# esp32cam.net
KiCad netlist of a schematic drawn in EAGLE
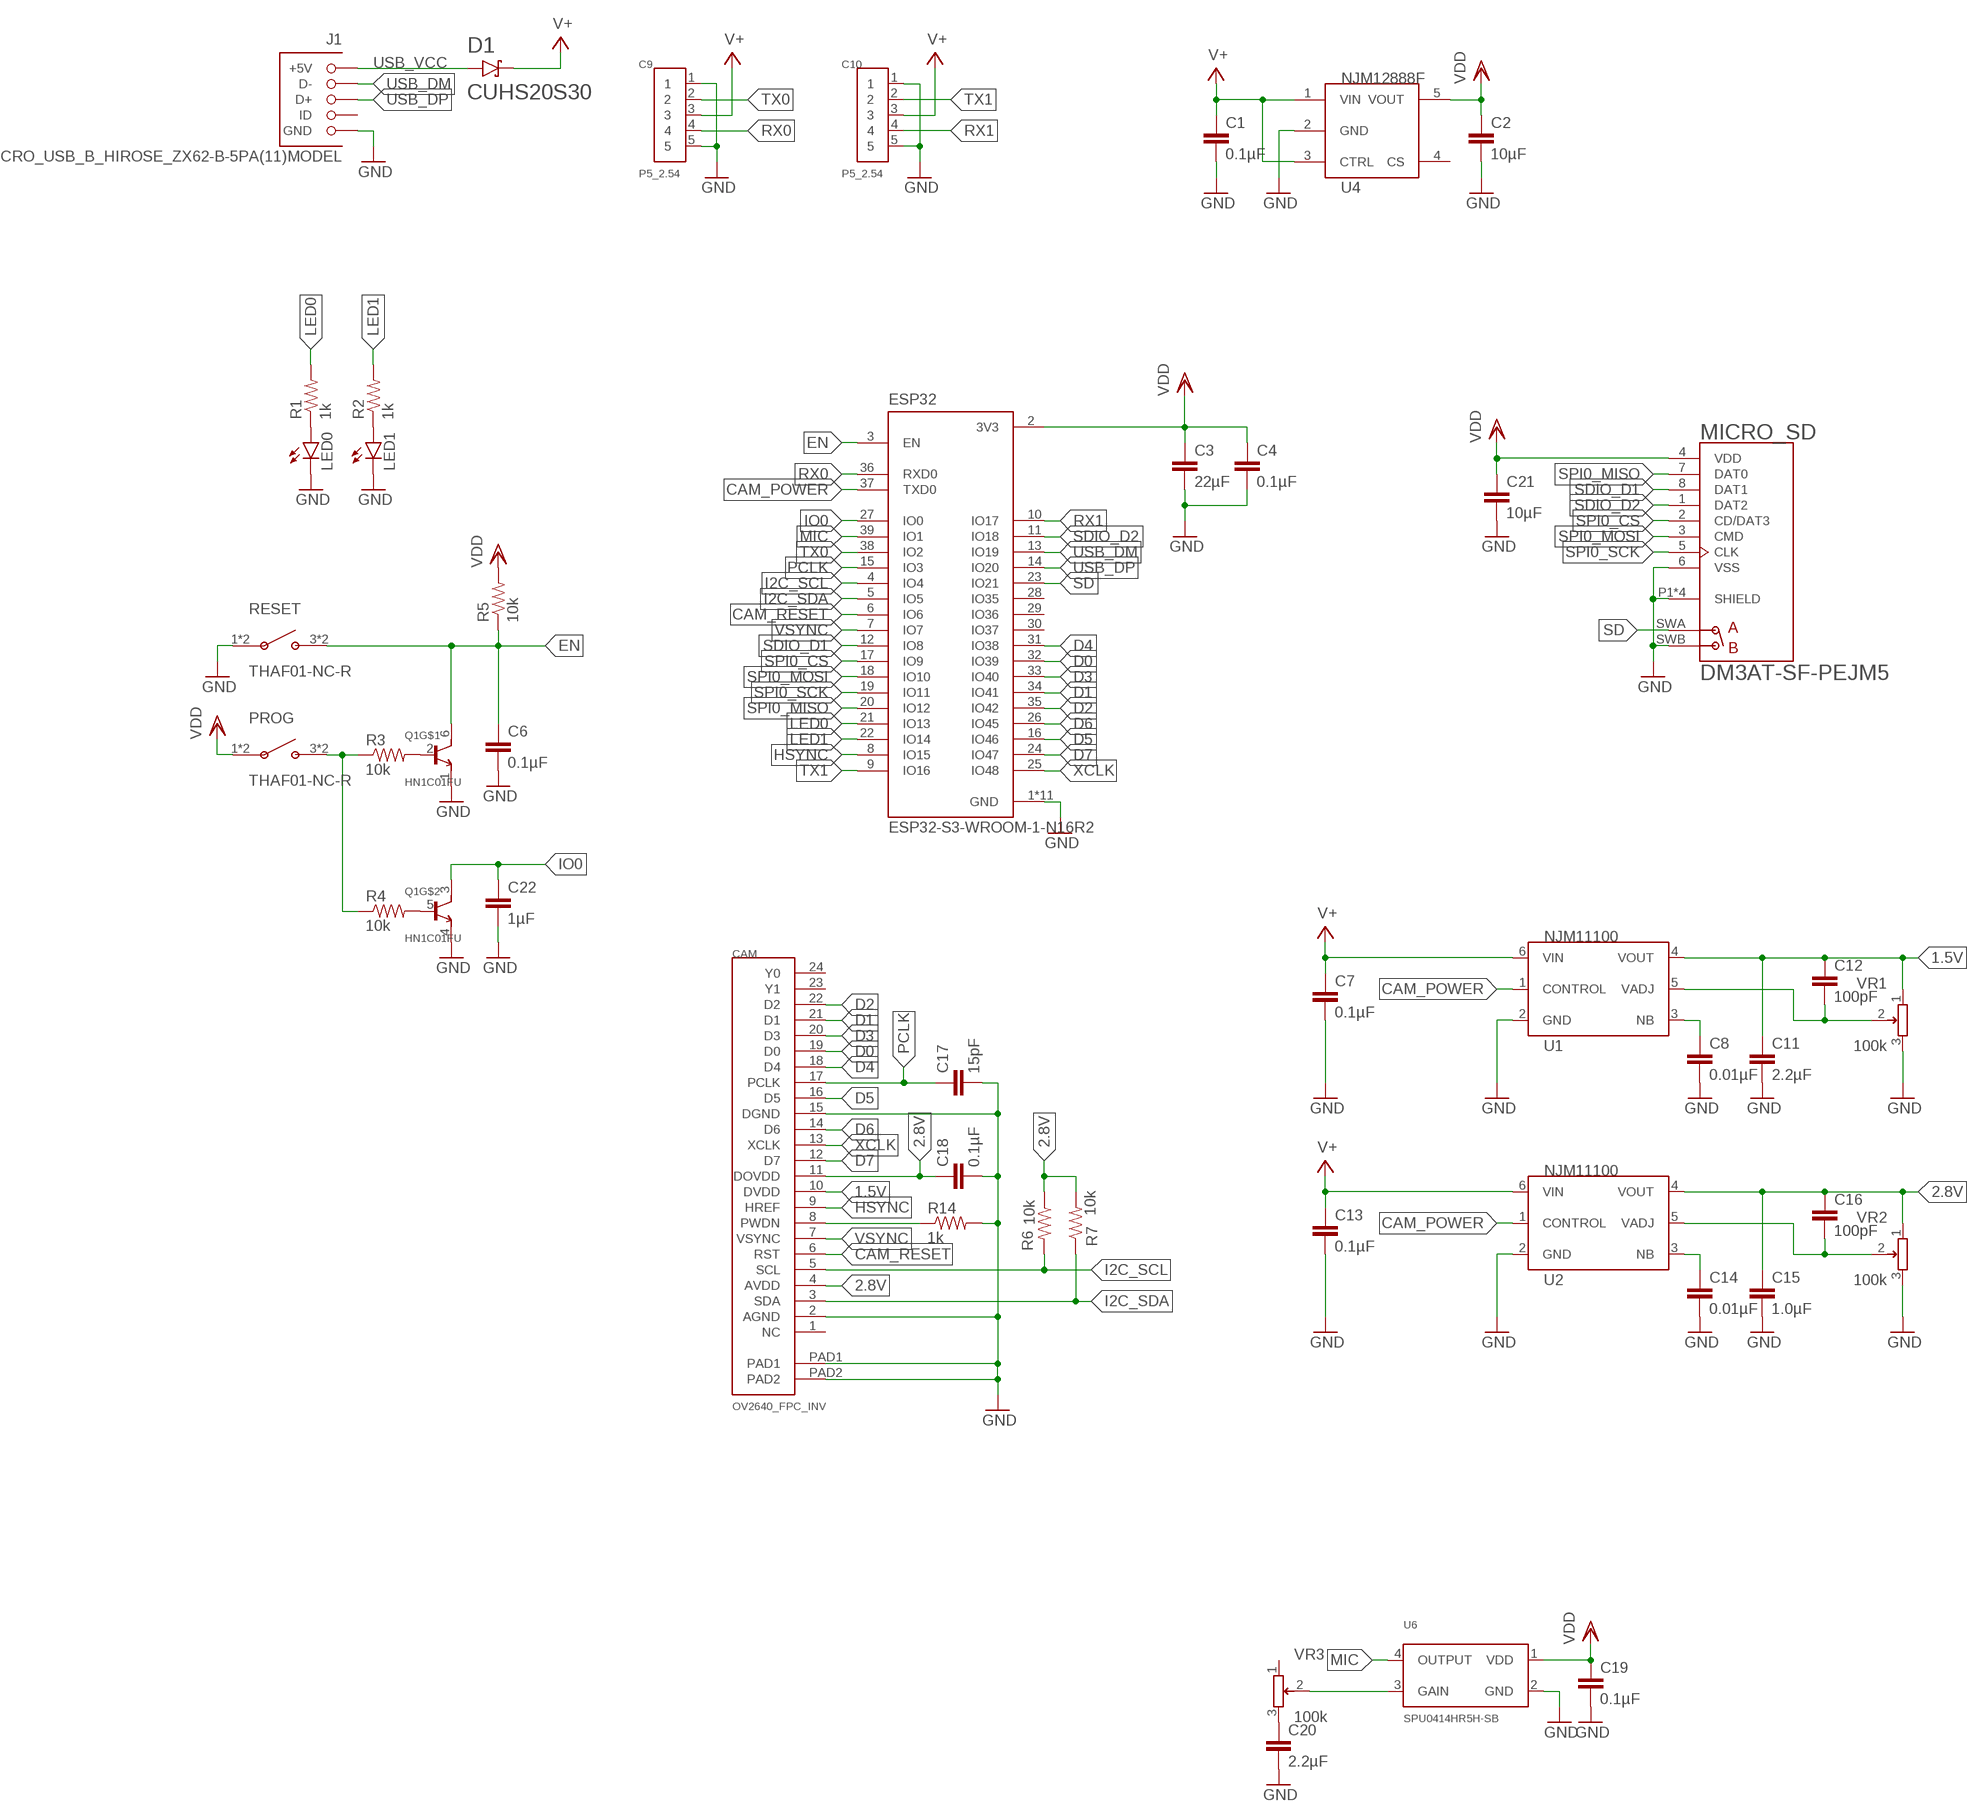
[diagram p0: schematic, sheet 1]

(export (version "E")
  (design (tool "Eeschema 10.0.6"))
  (components
    (comp (ref "C1")
      (value "0.1µF")
      (footprint "eagle-import:C0402")
      (libsource (lib "eagle-import") (part "C-EUC0402"))
    )
    (comp (ref "C2")
      (value "10µF")
      (footprint "eagle-import:C0402")
      (libsource (lib "eagle-import") (part "C-EUC0402"))
    )
    (comp (ref "C3")
      (value "22µF")
      (footprint "eagle-import:C0402")
      (libsource (lib "eagle-import") (part "C-EUC0402"))
    )
    (comp (ref "C4")
      (value "0.1µF")
      (footprint "eagle-import:C0402")
      (libsource (lib "eagle-import") (part "C-EUC0402"))
    )
    (comp (ref "C6")
      (value "0.1µF")
      (footprint "eagle-import:C0402")
      (libsource (lib "eagle-import") (part "C-EUC0402"))
    )
    (comp (ref "C7")
      (value "0.1µF")
      (footprint "eagle-import:C0402")
      (libsource (lib "eagle-import") (part "C-EUC0402"))
    )
    (comp (ref "C8")
      (value "0.01µF")
      (footprint "eagle-import:C0402")
      (libsource (lib "eagle-import") (part "C-EUC0402"))
    )
    (comp (ref "C9")
      (value "P5_2.54")
      (footprint "eagle-import:P5_2.54")
      (libsource (lib "eagle-import") (part "P5_2.54"))
    )
    (comp (ref "C10")
      (value "P5_2.54")
      (footprint "eagle-import:P5_2.54")
      (libsource (lib "eagle-import") (part "P5_2.54"))
    )
    (comp (ref "C11")
      (value "2.2µF")
      (footprint "eagle-import:C0402")
      (libsource (lib "eagle-import") (part "C-EUC0402"))
    )
    (comp (ref "C12")
      (value "100pF")
      (footprint "eagle-import:C0402")
      (libsource (lib "eagle-import") (part "C-EUC0402"))
    )
    (comp (ref "C13")
      (value "0.1µF")
      (footprint "eagle-import:C0402")
      (libsource (lib "eagle-import") (part "C-EUC0402"))
    )
    (comp (ref "C14")
      (value "0.01µF")
      (footprint "eagle-import:C0402")
      (libsource (lib "eagle-import") (part "C-EUC0402"))
    )
    (comp (ref "C15")
      (value "1.0µF")
      (footprint "eagle-import:C0402")
      (libsource (lib "eagle-import") (part "C-EUC0402"))
    )
    (comp (ref "C16")
      (value "100pF")
      (footprint "eagle-import:C0402")
      (libsource (lib "eagle-import") (part "C-EUC0402"))
    )
    (comp (ref "C17")
      (value "15pF")
      (footprint "eagle-import:C0402")
      (libsource (lib "eagle-import") (part "C-EUC0402"))
    )
    (comp (ref "C18")
      (value "0.1µF")
      (footprint "eagle-import:C0402")
      (libsource (lib "eagle-import") (part "C-EUC0402"))
    )
    (comp (ref "C19")
      (value "0.1µF")
      (footprint "eagle-import:C0402")
      (libsource (lib "eagle-import") (part "C-EUC0402"))
    )
    (comp (ref "C20")
      (value "2.2µF")
      (footprint "eagle-import:C0402")
      (libsource (lib "eagle-import") (part "C-EUC0402"))
    )
    (comp (ref "C21")
      (value "10µF")
      (footprint "eagle-import:C0402")
      (libsource (lib "eagle-import") (part "C-EUC0402"))
    )
    (comp (ref "C22")
      (value "1µF")
      (footprint "eagle-import:C0402")
      (libsource (lib "eagle-import") (part "C-EUC0402"))
    )
    (comp (ref "CAM")
      (value "OV2640_FPC_INV")
      (footprint "eagle-import:FH12-24S-0.5SH")
      (libsource (lib "eagle-import") (part "OV2640_FPC_INV"))
    )
    (comp (ref "D1")
      (value "CUHS20S30")
      (footprint "eagle-import:CUHS20S30")
      (libsource (lib "eagle-import") (part "CUHS20S30"))
    )
    (comp (ref "ESP32")
      (value "ESP32-S3-WROOM-1-N16R2")
      (footprint "eagle-import:XCVR_ESP32-S3-WROOM-1-N16R2")
      (fields (field (name "MF") "Espressif Systems"))
      (libsource (lib "eagle-import") (part "ESP32-S3-WROOM-1-N16R2"))
    )
    (comp (ref "J1")
      (value "MICRO_USB_B_HIROSE_ZX62-B-5PA(11)MODEL")
      (footprint "eagle-import:GHI-CONNECTORS_10118192-0001LF(MICRO-USB-B-AMPHENOL-FCI)")
      (libsource (lib "eagle-import") (part "MICRO_USB_B_HIROSE_ZX62-B-5PA(11)MODEL"))
    )
    (comp (ref "LED0")
      (value "LEDCHIPLED_0603")
      (footprint "eagle-import:CHIPLED_0603")
      (libsource (lib "eagle-import") (part "LEDCHIPLED_0603"))
    )
    (comp (ref "LED1")
      (value "LEDCHIPLED_0603")
      (footprint "eagle-import:CHIPLED_0603")
      (libsource (lib "eagle-import") (part "LEDCHIPLED_0603"))
    )
    (comp (ref "MICRO_SD")
      (value "DM3AT-SF-PEJM5")
      (footprint "eagle-import:HRS_DM3AT-SF-PEJM5")
      (fields (field (name "DIGI-KEY_PART_NUMBER") "HR1964CT-ND") (field (name "MF") "Hirose"))
      (libsource (lib "eagle-import") (part "DM3AT-SF-PEJM5"))
    )
    (comp (ref "PROG")
      (value "THAF01-NC-R")
      (footprint "eagle-import:THAF01-NC-R")
      (libsource (lib "eagle-import") (part "THAF01-NC-R"))
    )
    (comp (ref "Q1")
      (value "HN1C01FU")
      (footprint "eagle-import:SOT-363")
      (libsource (lib "eagle-import") (part "HN1C01FU"))
    )
    (comp (ref "R1")
      (value "1k")
      (footprint "eagle-import:R0402")
      (libsource (lib "eagle-import") (part "R-US_R0402"))
    )
    (comp (ref "R2")
      (value "1k")
      (footprint "eagle-import:R0402")
      (libsource (lib "eagle-import") (part "R-US_R0402"))
    )
    (comp (ref "R3")
      (value "10k")
      (footprint "eagle-import:R0402")
      (libsource (lib "eagle-import") (part "R-US_R0402"))
    )
    (comp (ref "R4")
      (value "10k")
      (footprint "eagle-import:R0402")
      (libsource (lib "eagle-import") (part "R-US_R0402"))
    )
    (comp (ref "R5")
      (value "10k")
      (footprint "eagle-import:R0402")
      (libsource (lib "eagle-import") (part "R-US_R0402"))
    )
    (comp (ref "R6")
      (value "10k")
      (footprint "eagle-import:R0402")
      (libsource (lib "eagle-import") (part "R-US_R0402"))
    )
    (comp (ref "R7")
      (value "10k")
      (footprint "eagle-import:R0402")
      (libsource (lib "eagle-import") (part "R-US_R0402"))
    )
    (comp (ref "R14")
      (value "1k")
      (footprint "eagle-import:R0402")
      (libsource (lib "eagle-import") (part "R-US_R0402"))
    )
    (comp (ref "RESET")
      (value "THAF01-NC-R")
      (footprint "eagle-import:THAF01-NC-R")
      (libsource (lib "eagle-import") (part "THAF01-NC-R"))
    )
    (comp (ref "U1")
      (value "NJM11100")
      (footprint "eagle-import:SOT95P240X110-6N")
      (libsource (lib "eagle-import") (part "NJM11100"))
    )
    (comp (ref "U2")
      (value "NJM11100")
      (footprint "eagle-import:SOT95P240X110-6N")
      (libsource (lib "eagle-import") (part "NJM11100"))
    )
    (comp (ref "U4")
      (value "NJM12888F")
      (footprint "eagle-import:SOT95P240X110-5N")
      (libsource (lib "eagle-import") (part "NJM12888F"))
    )
    (comp (ref "U6")
      (value "SPU0414HR5H-SB")
      (footprint "eagle-import:SPU0414HR5H-SB")
      (libsource (lib "eagle-import") (part "SPU0414HR5H-SB"))
    )
    (comp (ref "VR1")
      (value "100k")
      (footprint "eagle-import:PVZ3A")
      (libsource (lib "eagle-import") (part "PVZ3A"))
    )
    (comp (ref "VR2")
      (value "100k")
      (footprint "eagle-import:PVZ3A")
      (libsource (lib "eagle-import") (part "PVZ3A"))
    )
    (comp (ref "VR3")
      (value "100k")
      (footprint "eagle-import:PVZ3A")
      (libsource (lib "eagle-import") (part "PVZ3A"))
    )
  )
  (nets
    (net (code "1") (name "/USB_VCC") (class "Default")
      (node (ref "D1") (pin "A") (pinfunction "A_A") (pintype "bidirectional"))
      (node (ref "J1") (pin "VBUS") (pinfunction "+5V_VBUS") (pintype "bidirectional"))
    )
    (net (code "2") (name "1.5V") (class "Default")
      (node (ref "C11") (pin "1") (pinfunction "1_1") (pintype "passive"))
      (node (ref "C12") (pin "1") (pinfunction "1_1") (pintype "passive"))
      (node (ref "CAM") (pin "10") (pinfunction "DVDD_10") (pintype "power_in"))
      (node (ref "U1") (pin "4") (pinfunction "VOUT_4") (pintype "power_in"))
      (node (ref "VR1") (pin "1") (pinfunction "1_1") (pintype "bidirectional"))
    )
    (net (code "3") (name "2.8V") (class "Default")
      (node (ref "C15") (pin "1") (pinfunction "1_1") (pintype "passive"))
      (node (ref "C16") (pin "1") (pinfunction "1_1") (pintype "passive"))
      (node (ref "C18") (pin "1") (pinfunction "1_1") (pintype "passive"))
      (node (ref "CAM") (pin "11") (pinfunction "DOVDD_11") (pintype "power_in"))
      (node (ref "CAM") (pin "4") (pinfunction "AVDD_4") (pintype "power_in"))
      (node (ref "R6") (pin "1") (pinfunction "1_1") (pintype "passive"))
      (node (ref "R7") (pin "2") (pinfunction "2_2") (pintype "passive"))
      (node (ref "U2") (pin "4") (pinfunction "VOUT_4") (pintype "power_in"))
      (node (ref "VR2") (pin "1") (pinfunction "1_1") (pintype "bidirectional"))
    )
    (net (code "4") (name "CAM_POWER") (class "Default")
      (node (ref "ESP32") (pin "37") (pinfunction "TXD0_37") (pintype "bidirectional"))
      (node (ref "U1") (pin "1") (pinfunction "CONTROL_1") (pintype "input"))
      (node (ref "U2") (pin "1") (pinfunction "CONTROL_1") (pintype "input"))
    )
    (net (code "5") (name "CAM_RESET") (class "Default")
      (node (ref "CAM") (pin "6") (pinfunction "RST_6") (pintype "bidirectional"))
      (node (ref "ESP32") (pin "6") (pinfunction "IO6_6") (pintype "bidirectional"))
    )
    (net (code "6") (name "D0") (class "Default")
      (node (ref "CAM") (pin "19") (pinfunction "D0_19") (pintype "bidirectional"))
      (node (ref "ESP32") (pin "32") (pinfunction "IO39_32") (pintype "bidirectional"))
    )
    (net (code "7") (name "D1") (class "Default")
      (node (ref "CAM") (pin "21") (pinfunction "D1_21") (pintype "bidirectional"))
      (node (ref "ESP32") (pin "34") (pinfunction "IO41_34") (pintype "bidirectional"))
    )
    (net (code "8") (name "D2") (class "Default")
      (node (ref "CAM") (pin "22") (pinfunction "D2_22") (pintype "bidirectional"))
      (node (ref "ESP32") (pin "35") (pinfunction "IO42_35") (pintype "bidirectional"))
    )
    (net (code "9") (name "D3") (class "Default")
      (node (ref "CAM") (pin "20") (pinfunction "D3_20") (pintype "bidirectional"))
      (node (ref "ESP32") (pin "33") (pinfunction "IO40_33") (pintype "bidirectional"))
    )
    (net (code "10") (name "D4") (class "Default")
      (node (ref "CAM") (pin "18") (pinfunction "D4_18") (pintype "bidirectional"))
      (node (ref "ESP32") (pin "31") (pinfunction "IO38_31") (pintype "bidirectional"))
    )
    (net (code "11") (name "D5") (class "Default")
      (node (ref "CAM") (pin "16") (pinfunction "D5_16") (pintype "bidirectional"))
      (node (ref "ESP32") (pin "16") (pinfunction "IO46_16") (pintype "bidirectional"))
    )
    (net (code "12") (name "D6") (class "Default")
      (node (ref "CAM") (pin "14") (pinfunction "D6_14") (pintype "bidirectional"))
      (node (ref "ESP32") (pin "26") (pinfunction "IO45_26") (pintype "bidirectional"))
    )
    (net (code "13") (name "D7") (class "Default")
      (node (ref "CAM") (pin "12") (pinfunction "D7_12") (pintype "bidirectional"))
      (node (ref "ESP32") (pin "24") (pinfunction "IO47_24") (pintype "bidirectional"))
    )
    (net (code "14") (name "EN") (class "Default")
      (node (ref "C6") (pin "1") (pinfunction "1_1") (pintype "passive"))
      (node (ref "ESP32") (pin "3") (pinfunction "EN_3") (pintype "input"))
      (node (ref "Q1") (pin "6") (pinfunction "C_6") (pintype "bidirectional"))
      (node (ref "R5") (pin "1") (pinfunction "1_1") (pintype "passive"))
      (node (ref "RESET") (pin "3") (pinfunction "B_3") (pintype "bidirectional"))
      (node (ref "RESET") (pin "4") (pinfunction "B_4") (pintype "bidirectional"))
    )
    (net (code "15") (name "GND") (class "Default")
      (node (ref "C1") (pin "2") (pinfunction "2_2") (pintype "passive"))
      (node (ref "C10") (pin "1") (pinfunction "1_1") (pintype "bidirectional"))
      (node (ref "C10") (pin "5") (pinfunction "5_5") (pintype "bidirectional"))
      (node (ref "C11") (pin "2") (pinfunction "2_2") (pintype "passive"))
      (node (ref "C13") (pin "2") (pinfunction "2_2") (pintype "passive"))
      (node (ref "C14") (pin "2") (pinfunction "2_2") (pintype "passive"))
      (node (ref "C15") (pin "2") (pinfunction "2_2") (pintype "passive"))
      (node (ref "C17") (pin "2") (pinfunction "2_2") (pintype "passive"))
      (node (ref "C18") (pin "2") (pinfunction "2_2") (pintype "passive"))
      (node (ref "C19") (pin "2") (pinfunction "2_2") (pintype "passive"))
      (node (ref "C2") (pin "2") (pinfunction "2_2") (pintype "passive"))
      (node (ref "C20") (pin "2") (pinfunction "2_2") (pintype "passive"))
      (node (ref "C21") (pin "2") (pinfunction "2_2") (pintype "passive"))
      (node (ref "C22") (pin "2") (pinfunction "2_2") (pintype "passive"))
      (node (ref "C3") (pin "2") (pinfunction "2_2") (pintype "passive"))
      (node (ref "C4") (pin "2") (pinfunction "2_2") (pintype "passive"))
      (node (ref "C6") (pin "2") (pinfunction "2_2") (pintype "passive"))
      (node (ref "C7") (pin "2") (pinfunction "2_2") (pintype "passive"))
      (node (ref "C8") (pin "2") (pinfunction "2_2") (pintype "passive"))
      (node (ref "C9") (pin "1") (pinfunction "1_1") (pintype "bidirectional"))
      (node (ref "C9") (pin "5") (pinfunction "5_5") (pintype "bidirectional"))
      (node (ref "CAM") (pin "15") (pinfunction "DGND_15") (pintype "power_in"))
      (node (ref "CAM") (pin "2") (pinfunction "AGND_2") (pintype "power_in"))
      (node (ref "CAM") (pin "PAD1") (pinfunction "PAD1_PAD1") (pintype "bidirectional"))
      (node (ref "CAM") (pin "PAD2") (pinfunction "PAD2_PAD2") (pintype "bidirectional"))
      (node (ref "ESP32") (pin "1") (pinfunction "GND_1") (pintype "power_in"))
      (node (ref "ESP32") (pin "40") (pinfunction "GND_40") (pintype "power_in"))
      (node (ref "ESP32") (pin "41_1") (pinfunction "GND_41_1") (pintype "power_in"))
      (node (ref "ESP32") (pin "41_2") (pinfunction "GND_41_2") (pintype "power_in"))
      (node (ref "ESP32") (pin "41_3") (pinfunction "GND_41_3") (pintype "power_in"))
      (node (ref "ESP32") (pin "41_4") (pinfunction "GND_41_4") (pintype "power_in"))
      (node (ref "ESP32") (pin "41_5") (pinfunction "GND_41_5") (pintype "power_in"))
      (node (ref "ESP32") (pin "41_6") (pinfunction "GND_41_6") (pintype "power_in"))
      (node (ref "ESP32") (pin "41_7") (pinfunction "GND_41_7") (pintype "power_in"))
      (node (ref "ESP32") (pin "41_8") (pinfunction "GND_41_8") (pintype "power_in"))
      (node (ref "ESP32") (pin "41_9") (pinfunction "GND_41_9") (pintype "power_in"))
      (node (ref "J1") (pin "CGND1") (pinfunction "GND_CGND1") (pintype "bidirectional"))
      (node (ref "J1") (pin "CGND2") (pinfunction "GND_CGND2") (pintype "bidirectional"))
      (node (ref "J1") (pin "CGND3") (pinfunction "GND_CGND3") (pintype "bidirectional"))
      (node (ref "J1") (pin "CGND4") (pinfunction "GND_CGND4") (pintype "bidirectional"))
      (node (ref "J1") (pin "CGND5") (pinfunction "GND_CGND5") (pintype "bidirectional"))
      (node (ref "J1") (pin "CGND6") (pinfunction "GND_CGND6") (pintype "bidirectional"))
      (node (ref "J1") (pin "GND") (pinfunction "GND_GND") (pintype "bidirectional"))
      (node (ref "LED0") (pin "C") (pinfunction "C_C") (pintype "passive"))
      (node (ref "LED1") (pin "C") (pinfunction "C_C") (pintype "passive"))
      (node (ref "MICRO_SD") (pin "6") (pinfunction "VSS_6") (pintype "power_in"))
      (node (ref "MICRO_SD") (pin "P1") (pinfunction "SHIELD_P1") (pintype "passive"))
      (node (ref "MICRO_SD") (pin "P2") (pinfunction "SHIELD_P2") (pintype "passive"))
      (node (ref "MICRO_SD") (pin "P3") (pinfunction "SHIELD_P3") (pintype "passive"))
      (node (ref "MICRO_SD") (pin "P4") (pinfunction "SHIELD_P4") (pintype "passive"))
      (node (ref "MICRO_SD") (pin "SWB") (pinfunction "B_SWB") (pintype "bidirectional"))
      (node (ref "Q1") (pin "1") (pinfunction "E_1") (pintype "bidirectional"))
      (node (ref "Q1") (pin "4") (pinfunction "E_4") (pintype "bidirectional"))
      (node (ref "R14") (pin "2") (pinfunction "2_2") (pintype "passive"))
      (node (ref "RESET") (pin "1") (pinfunction "A_1") (pintype "bidirectional"))
      (node (ref "RESET") (pin "2") (pinfunction "A_2") (pintype "bidirectional"))
      (node (ref "U1") (pin "2") (pinfunction "GND_2") (pintype "power_in"))
      (node (ref "U2") (pin "2") (pinfunction "GND_2") (pintype "power_in"))
      (node (ref "U4") (pin "2") (pinfunction "GND_2") (pintype "power_in"))
      (node (ref "U6") (pin "2") (pinfunction "GND_2") (pintype "bidirectional"))
      (node (ref "VR1") (pin "3") (pinfunction "3_3") (pintype "bidirectional"))
      (node (ref "VR2") (pin "3") (pinfunction "3_3") (pintype "bidirectional"))
    )
    (net (code "16") (name "HSYNC") (class "Default")
      (node (ref "CAM") (pin "9") (pinfunction "HREF_9") (pintype "bidirectional"))
      (node (ref "ESP32") (pin "8") (pinfunction "IO15_8") (pintype "bidirectional"))
    )
    (net (code "17") (name "I2C_SCL") (class "Default")
      (node (ref "CAM") (pin "5") (pinfunction "SCL_5") (pintype "bidirectional"))
      (node (ref "ESP32") (pin "4") (pinfunction "IO4_4") (pintype "bidirectional"))
      (node (ref "R6") (pin "2") (pinfunction "2_2") (pintype "passive"))
    )
    (net (code "18") (name "I2C_SDA") (class "Default")
      (node (ref "CAM") (pin "3") (pinfunction "SDA_3") (pintype "bidirectional"))
      (node (ref "ESP32") (pin "5") (pinfunction "IO5_5") (pintype "bidirectional"))
      (node (ref "R7") (pin "1") (pinfunction "1_1") (pintype "passive"))
    )
    (net (code "19") (name "IO0") (class "Default")
      (node (ref "C22") (pin "1") (pinfunction "1_1") (pintype "passive"))
      (node (ref "ESP32") (pin "27") (pinfunction "IO0_27") (pintype "bidirectional"))
      (node (ref "Q1") (pin "3") (pinfunction "C_3") (pintype "bidirectional"))
    )
    (net (code "20") (name "LED0") (class "Default")
      (node (ref "ESP32") (pin "21") (pinfunction "IO13_21") (pintype "bidirectional"))
      (node (ref "R1") (pin "2") (pinfunction "2_2") (pintype "passive"))
    )
    (net (code "21") (name "LED1") (class "Default")
      (node (ref "ESP32") (pin "22") (pinfunction "IO14_22") (pintype "bidirectional"))
      (node (ref "R2") (pin "2") (pinfunction "2_2") (pintype "passive"))
    )
    (net (code "22") (name "MIC") (class "Default")
      (node (ref "ESP32") (pin "39") (pinfunction "IO1_39") (pintype "bidirectional"))
      (node (ref "U6") (pin "4") (pinfunction "OUTPUT_4") (pintype "bidirectional"))
    )
    (net (code "23") (name "Net-(C20-Pad1)") (class "Default")
      (node (ref "C20") (pin "1") (pinfunction "1_1") (pintype "passive"))
      (node (ref "VR3") (pin "3") (pinfunction "3_3") (pintype "bidirectional"))
    )
    (net (code "24") (name "Net-(CAM-PWDN)") (class "Default")
      (node (ref "CAM") (pin "8") (pinfunction "PWDN_8") (pintype "bidirectional"))
      (node (ref "R14") (pin "1") (pinfunction "1_1") (pintype "passive"))
    )
    (net (code "25") (name "Net-(LED0-PadA)") (class "Default")
      (node (ref "LED0") (pin "A") (pinfunction "A_A") (pintype "passive"))
      (node (ref "R1") (pin "1") (pinfunction "1_1") (pintype "passive"))
    )
    (net (code "26") (name "Net-(LED1-PadA)") (class "Default")
      (node (ref "LED1") (pin "A") (pinfunction "A_A") (pintype "passive"))
      (node (ref "R2") (pin "1") (pinfunction "1_1") (pintype "passive"))
    )
    (net (code "27") (name "Net-(PROG-B-Pad3)") (class "Default")
      (node (ref "PROG") (pin "3") (pinfunction "B_3") (pintype "bidirectional"))
      (node (ref "PROG") (pin "4") (pinfunction "B_4") (pintype "bidirectional"))
      (node (ref "R3") (pin "1") (pinfunction "1_1") (pintype "passive"))
      (node (ref "R4") (pin "1") (pinfunction "1_1") (pintype "passive"))
    )
    (net (code "28") (name "Net-(Q1A-B)") (class "Default")
      (node (ref "Q1") (pin "2") (pinfunction "B_2") (pintype "bidirectional"))
      (node (ref "R3") (pin "2") (pinfunction "2_2") (pintype "passive"))
    )
    (net (code "29") (name "Net-(Q1B-B)") (class "Default")
      (node (ref "Q1") (pin "5") (pinfunction "B_5") (pintype "bidirectional"))
      (node (ref "R4") (pin "2") (pinfunction "2_2") (pintype "passive"))
    )
    (net (code "30") (name "Net-(U1-NB)") (class "Default")
      (node (ref "C8") (pin "1") (pinfunction "1_1") (pintype "passive"))
      (node (ref "U1") (pin "3") (pinfunction "NB_3") (pintype "bidirectional"))
    )
    (net (code "31") (name "Net-(U1-VADJ)") (class "Default")
      (node (ref "C12") (pin "2") (pinfunction "2_2") (pintype "passive"))
      (node (ref "U1") (pin "5") (pinfunction "VADJ_5") (pintype "input"))
      (node (ref "VR1") (pin "2") (pinfunction "2_2") (pintype "bidirectional"))
    )
    (net (code "32") (name "Net-(U2-NB)") (class "Default")
      (node (ref "C14") (pin "1") (pinfunction "1_1") (pintype "passive"))
      (node (ref "U2") (pin "3") (pinfunction "NB_3") (pintype "bidirectional"))
    )
    (net (code "33") (name "Net-(U2-VADJ)") (class "Default")
      (node (ref "C16") (pin "2") (pinfunction "2_2") (pintype "passive"))
      (node (ref "U2") (pin "5") (pinfunction "VADJ_5") (pintype "input"))
      (node (ref "VR2") (pin "2") (pinfunction "2_2") (pintype "bidirectional"))
    )
    (net (code "34") (name "Net-(U6-GAIN)") (class "Default")
      (node (ref "U6") (pin "3") (pinfunction "GAIN_3") (pintype "bidirectional"))
      (node (ref "VR3") (pin "2") (pinfunction "2_2") (pintype "bidirectional"))
    )
    (net (code "35") (name "PCLK") (class "Default")
      (node (ref "C17") (pin "1") (pinfunction "1_1") (pintype "passive"))
      (node (ref "CAM") (pin "17") (pinfunction "PCLK_17") (pintype "bidirectional"))
      (node (ref "ESP32") (pin "15") (pinfunction "IO3_15") (pintype "bidirectional"))
    )
    (net (code "36") (name "RX0") (class "Default")
      (node (ref "C9") (pin "4") (pinfunction "4_4") (pintype "bidirectional"))
      (node (ref "ESP32") (pin "36") (pinfunction "RXD0_36") (pintype "bidirectional"))
    )
    (net (code "37") (name "RX1") (class "Default")
      (node (ref "C10") (pin "4") (pinfunction "4_4") (pintype "bidirectional"))
      (node (ref "ESP32") (pin "10") (pinfunction "IO17_10") (pintype "bidirectional"))
    )
    (net (code "38") (name "SD") (class "Default")
      (node (ref "ESP32") (pin "23") (pinfunction "IO21_23") (pintype "bidirectional"))
      (node (ref "MICRO_SD") (pin "SWA") (pinfunction "A_SWA") (pintype "bidirectional"))
    )
    (net (code "39") (name "SDIO_D1") (class "Default")
      (node (ref "ESP32") (pin "12") (pinfunction "IO8_12") (pintype "bidirectional"))
      (node (ref "MICRO_SD") (pin "8") (pinfunction "DAT1_8") (pintype "bidirectional"))
    )
    (net (code "40") (name "SDIO_D2") (class "Default")
      (node (ref "ESP32") (pin "11") (pinfunction "IO18_11") (pintype "bidirectional"))
      (node (ref "MICRO_SD") (pin "1") (pinfunction "DAT2_1") (pintype "bidirectional"))
    )
    (net (code "41") (name "SPI0_CS") (class "Default")
      (node (ref "ESP32") (pin "17") (pinfunction "IO9_17") (pintype "bidirectional"))
      (node (ref "MICRO_SD") (pin "2") (pinfunction "CD/DAT3_2") (pintype "bidirectional"))
    )
    (net (code "42") (name "SPI0_MISO") (class "Default")
      (node (ref "ESP32") (pin "20") (pinfunction "IO12_20") (pintype "bidirectional"))
      (node (ref "MICRO_SD") (pin "7") (pinfunction "DAT0_7") (pintype "bidirectional"))
    )
    (net (code "43") (name "SPI0_MOSI") (class "Default")
      (node (ref "ESP32") (pin "18") (pinfunction "IO10_18") (pintype "bidirectional"))
      (node (ref "MICRO_SD") (pin "3") (pinfunction "CMD_3") (pintype "bidirectional"))
    )
    (net (code "44") (name "SPI0_SCK") (class "Default")
      (node (ref "ESP32") (pin "19") (pinfunction "IO11_19") (pintype "bidirectional"))
      (node (ref "MICRO_SD") (pin "5") (pinfunction "CLK_5") (pintype "bidirectional"))
    )
    (net (code "45") (name "TX0") (class "Default")
      (node (ref "C9") (pin "2") (pinfunction "2_2") (pintype "bidirectional"))
      (node (ref "ESP32") (pin "38") (pinfunction "IO2_38") (pintype "bidirectional"))
    )
    (net (code "46") (name "TX1") (class "Default")
      (node (ref "C10") (pin "2") (pinfunction "2_2") (pintype "bidirectional"))
      (node (ref "ESP32") (pin "9") (pinfunction "IO16_9") (pintype "bidirectional"))
    )
    (net (code "47") (name "USB_DM") (class "Default")
      (node (ref "ESP32") (pin "13") (pinfunction "IO19_13") (pintype "bidirectional"))
      (node (ref "J1") (pin "D-") (pinfunction "D-_D-") (pintype "bidirectional"))
    )
    (net (code "48") (name "USB_DP") (class "Default")
      (node (ref "ESP32") (pin "14") (pinfunction "IO20_14") (pintype "bidirectional"))
      (node (ref "J1") (pin "D+") (pinfunction "D+_D+") (pintype "bidirectional"))
    )
    (net (code "49") (name "V+") (class "Default")
      (node (ref "C1") (pin "1") (pinfunction "1_1") (pintype "passive"))
      (node (ref "C10") (pin "3") (pinfunction "3_3") (pintype "bidirectional"))
      (node (ref "C13") (pin "1") (pinfunction "1_1") (pintype "passive"))
      (node (ref "C7") (pin "1") (pinfunction "1_1") (pintype "passive"))
      (node (ref "C9") (pin "3") (pinfunction "3_3") (pintype "bidirectional"))
      (node (ref "D1") (pin "C") (pinfunction "C_C") (pintype "bidirectional"))
      (node (ref "U1") (pin "6") (pinfunction "VIN_6") (pintype "power_in"))
      (node (ref "U2") (pin "6") (pinfunction "VIN_6") (pintype "power_in"))
      (node (ref "U4") (pin "1") (pinfunction "VIN_1") (pintype "power_in"))
      (node (ref "U4") (pin "3") (pinfunction "CTRL_3") (pintype "input"))
    )
    (net (code "50") (name "VDD") (class "Default")
      (node (ref "C19") (pin "1") (pinfunction "1_1") (pintype "passive"))
      (node (ref "C2") (pin "1") (pinfunction "1_1") (pintype "passive"))
      (node (ref "C21") (pin "1") (pinfunction "1_1") (pintype "passive"))
      (node (ref "C3") (pin "1") (pinfunction "1_1") (pintype "passive"))
      (node (ref "C4") (pin "1") (pinfunction "1_1") (pintype "passive"))
      (node (ref "ESP32") (pin "2") (pinfunction "3V3_2") (pintype "power_in"))
      (node (ref "MICRO_SD") (pin "4") (pinfunction "VDD_4") (pintype "power_in"))
      (node (ref "PROG") (pin "1") (pinfunction "A_1") (pintype "bidirectional"))
      (node (ref "PROG") (pin "2") (pinfunction "A_2") (pintype "bidirectional"))
      (node (ref "R5") (pin "2") (pinfunction "2_2") (pintype "passive"))
      (node (ref "U4") (pin "5") (pinfunction "VOUT_5") (pintype "power_in"))
      (node (ref "U6") (pin "1") (pinfunction "VDD_1") (pintype "bidirectional"))
    )
    (net (code "51") (name "VSYNC") (class "Default")
      (node (ref "CAM") (pin "7") (pinfunction "VSYNC_7") (pintype "bidirectional"))
      (node (ref "ESP32") (pin "7") (pinfunction "IO7_7") (pintype "bidirectional"))
    )
    (net (code "52") (name "XCLK") (class "Default")
      (node (ref "CAM") (pin "13") (pinfunction "XCLK_13") (pintype "bidirectional"))
      (node (ref "ESP32") (pin "25") (pinfunction "IO48_25") (pintype "bidirectional"))
    )
    (net (code "53") (name "unconnected-(CAM-NC-Pad1)") (class "Default")
      (node (ref "CAM") (pin "1") (pinfunction "NC_1") (pintype "bidirectional"))
    )
    (net (code "54") (name "unconnected-(CAM-Y0-Pad24)") (class "Default")
      (node (ref "CAM") (pin "24") (pinfunction "Y0_24") (pintype "bidirectional"))
    )
    (net (code "55") (name "unconnected-(CAM-Y1-Pad23)") (class "Default")
      (node (ref "CAM") (pin "23") (pinfunction "Y1_23") (pintype "bidirectional"))
    )
    (net (code "56") (name "unconnected-(ESP32-IO35-Pad28)") (class "Default")
      (node (ref "ESP32") (pin "28") (pinfunction "IO35_28") (pintype "bidirectional"))
    )
    (net (code "57") (name "unconnected-(ESP32-IO36-Pad29)") (class "Default")
      (node (ref "ESP32") (pin "29") (pinfunction "IO36_29") (pintype "bidirectional"))
    )
    (net (code "58") (name "unconnected-(ESP32-IO37-Pad30)") (class "Default")
      (node (ref "ESP32") (pin "30") (pinfunction "IO37_30") (pintype "bidirectional"))
    )
    (net (code "59") (name "unconnected-(J1-PadID)") (class "Default")
      (node (ref "J1") (pin "ID") (pinfunction "ID_ID") (pintype "bidirectional"))
    )
    (net (code "60") (name "unconnected-(U4-CS-Pad4)") (class "Default")
      (node (ref "U4") (pin "4") (pinfunction "CS_4") (pintype "input"))
    )
    (net (code "61") (name "unconnected-(VR3-Pad1)") (class "Default")
      (node (ref "VR3") (pin "1") (pinfunction "1_1") (pintype "bidirectional"))
    )
  )
)
